# Connectors.net
KiCad netlist of a schematic drawn in Altium Designer
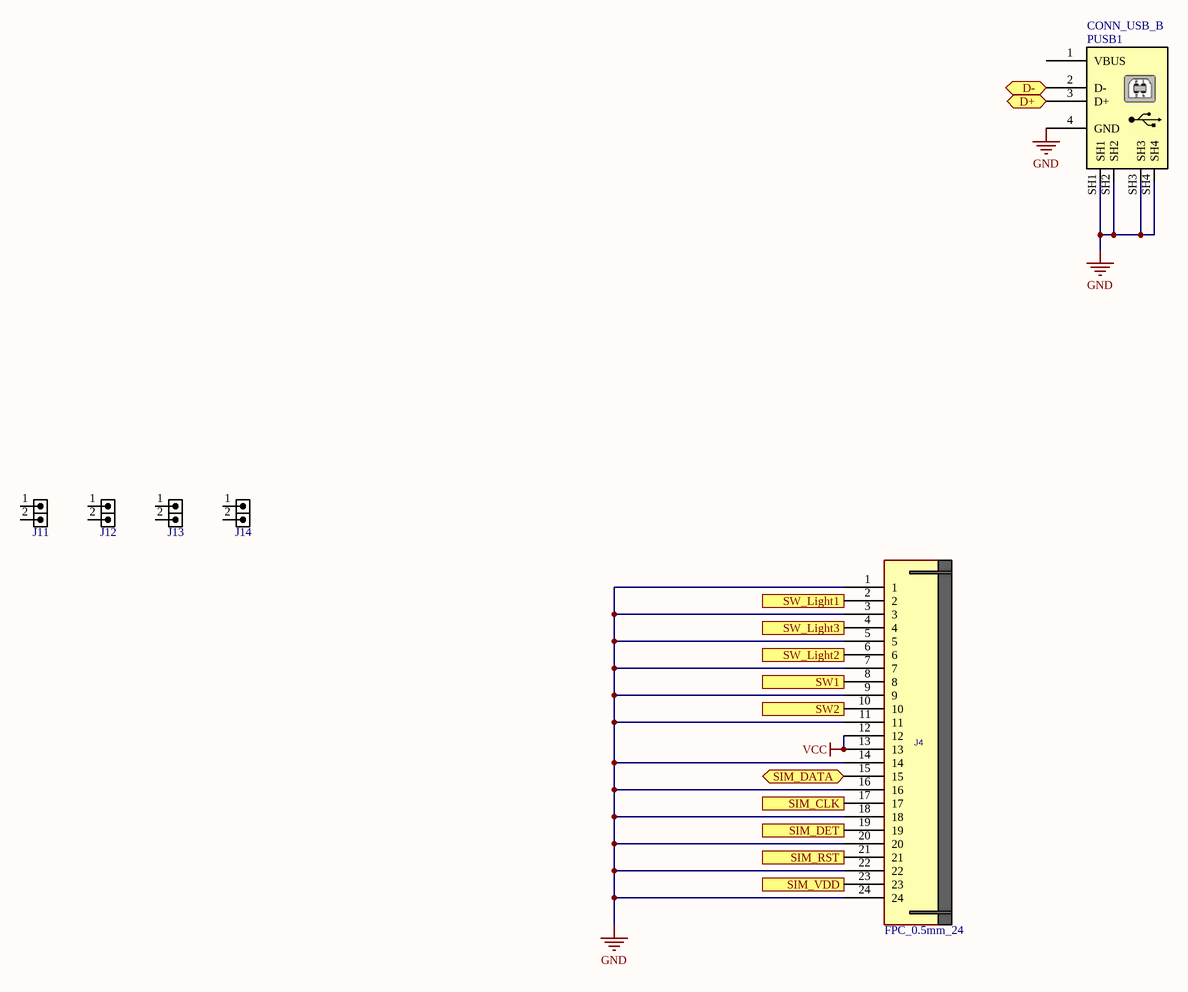
[diagram p0: Connectors.SchDoc]

(export (version "E")
  (design (tool "Eeschema 10.0.6"))
  (components
    (comp (ref "J4")
      (value "FPC_0.5mm_24")
      (description "CONN, FPC, 0.50mm pitch, RightAngle, Bot. Contact")
      (fields
        (field (name "MANF") "MOLEX, Hirose, FCI")
        (field (name "MANF_P#") "52437-2433, FH12-24S-0.5SH(55), SFV24R-1ST")
      )
      (libsource (lib "CONNECTOR") (part "FPC50_24"))
    )
    (comp (ref "J11")
      (value "HDRM2")
      (footprint "HDR_M_1X2")
      (description "CONN, HEADER, Male, pitch: 2.54mm, 2POS")
      (libsource (lib "CONNECTOR HDR") (part "HDR_M_1X2"))
    )
    (comp (ref "J12")
      (value "HDRM2")
      (footprint "HDR_M_1X2")
      (description "CONN, HEADER, Male, pitch: 2.54mm, 2POS")
      (libsource (lib "CONNECTOR HDR") (part "HDR_M_1X2"))
    )
    (comp (ref "J13")
      (value "HDRM2")
      (footprint "HDR_M_1X2")
      (description "CONN, HEADER, Male, pitch: 2.54mm, 2POS")
      (libsource (lib "CONNECTOR HDR") (part "HDR_M_1X2"))
    )
    (comp (ref "J14")
      (value "HDRM2")
      (footprint "HDR_M_1X2")
      (description "CONN, HEADER, Male, pitch: 2.54mm, 2POS")
      (libsource (lib "CONNECTOR HDR") (part "HDR_M_1X2"))
    )
    (comp (ref "PUSB1")
      (value "CONN_USB_B")
      (footprint "USB_B_ST")
      (description "CONN, USB, B, STRAIGHT, THD")
      (libsource (lib "CONNECTOR") (part "USB_B_ST"))
    )
  )
  (nets
    (net (code "1") (name "/D+") (class "Default")
      (node (ref "PUSB1") (pin "3") (pinfunction "D+_3") (pintype "passive"))
    )
    (net (code "2") (name "/D-") (class "Default")
      (node (ref "PUSB1") (pin "2") (pinfunction "D-_2") (pintype "passive"))
    )
    (net (code "3") (name "/SIM_CLK") (class "Default")
      (node (ref "J4") (pin "17") (pinfunction "17_17") (pintype "passive"))
    )
    (net (code "4") (name "/SIM_DATA") (class "Default")
      (node (ref "J4") (pin "15") (pinfunction "15_15") (pintype "passive"))
    )
    (net (code "5") (name "/SIM_DET") (class "Default")
      (node (ref "J4") (pin "19") (pinfunction "19_19") (pintype "passive"))
    )
    (net (code "6") (name "/SIM_RST") (class "Default")
      (node (ref "J4") (pin "21") (pinfunction "21_21") (pintype "passive"))
    )
    (net (code "7") (name "/SIM_VDD") (class "Default")
      (node (ref "J4") (pin "23") (pinfunction "23_23") (pintype "passive"))
    )
    (net (code "8") (name "/SW1") (class "Default")
      (node (ref "J4") (pin "8") (pinfunction "8_8") (pintype "passive"))
    )
    (net (code "9") (name "/SW2") (class "Default")
      (node (ref "J4") (pin "10") (pinfunction "10_10") (pintype "passive"))
    )
    (net (code "10") (name "/SW_Light1") (class "Default")
      (node (ref "J4") (pin "2") (pinfunction "2_2") (pintype "passive"))
    )
    (net (code "11") (name "/SW_Light2") (class "Default")
      (node (ref "J4") (pin "6") (pinfunction "6_6") (pintype "passive"))
    )
    (net (code "12") (name "/SW_Light3") (class "Default")
      (node (ref "J4") (pin "4") (pinfunction "4_4") (pintype "passive"))
    )
    (net (code "13") (name "GND") (class "Default")
      (node (ref "J4") (pin "1") (pinfunction "1_1") (pintype "passive"))
      (node (ref "J4") (pin "11") (pinfunction "11_11") (pintype "passive"))
      (node (ref "J4") (pin "14") (pinfunction "14_14") (pintype "passive"))
      (node (ref "J4") (pin "16") (pinfunction "16_16") (pintype "passive"))
      (node (ref "J4") (pin "18") (pinfunction "18_18") (pintype "passive"))
      (node (ref "J4") (pin "20") (pinfunction "20_20") (pintype "passive"))
      (node (ref "J4") (pin "22") (pinfunction "22_22") (pintype "passive"))
      (node (ref "J4") (pin "24") (pinfunction "24_24") (pintype "passive"))
      (node (ref "J4") (pin "3") (pinfunction "3_3") (pintype "passive"))
      (node (ref "J4") (pin "5") (pinfunction "5_5") (pintype "passive"))
      (node (ref "J4") (pin "7") (pinfunction "7_7") (pintype "passive"))
      (node (ref "J4") (pin "9") (pinfunction "9_9") (pintype "passive"))
      (node (ref "PUSB1") (pin "4") (pinfunction "GND_4") (pintype "power_in"))
      (node (ref "PUSB1") (pin "SH1") (pinfunction "SH1_SH1") (pintype "passive"))
      (node (ref "PUSB1") (pin "SH2") (pinfunction "SH2_SH2") (pintype "passive"))
      (node (ref "PUSB1") (pin "SH3") (pinfunction "SH3_SH3") (pintype "passive"))
      (node (ref "PUSB1") (pin "SH4") (pinfunction "SH4_SH4") (pintype "passive"))
    )
    (net (code "14") (name "VCC") (class "Default")
      (node (ref "J4") (pin "12") (pinfunction "12_12") (pintype "passive"))
      (node (ref "J4") (pin "13") (pinfunction "13_13") (pintype "passive"))
    )
    (net (code "15") (name "unconnected-(J11-Pad1)") (class "Default")
      (node (ref "J11") (pin "1") (pinfunction "1_1") (pintype "passive"))
    )
    (net (code "16") (name "unconnected-(J11-Pad2)") (class "Default")
      (node (ref "J11") (pin "2") (pinfunction "2_2") (pintype "passive"))
    )
    (net (code "17") (name "unconnected-(J12-Pad1)") (class "Default")
      (node (ref "J12") (pin "1") (pinfunction "1_1") (pintype "passive"))
    )
    (net (code "18") (name "unconnected-(J12-Pad2)") (class "Default")
      (node (ref "J12") (pin "2") (pinfunction "2_2") (pintype "passive"))
    )
    (net (code "19") (name "unconnected-(J13-Pad1)") (class "Default")
      (node (ref "J13") (pin "1") (pinfunction "1_1") (pintype "passive"))
    )
    (net (code "20") (name "unconnected-(J13-Pad2)") (class "Default")
      (node (ref "J13") (pin "2") (pinfunction "2_2") (pintype "passive"))
    )
    (net (code "21") (name "unconnected-(J14-Pad1)") (class "Default")
      (node (ref "J14") (pin "1") (pinfunction "1_1") (pintype "passive"))
    )
    (net (code "22") (name "unconnected-(J14-Pad2)") (class "Default")
      (node (ref "J14") (pin "2") (pinfunction "2_2") (pintype "passive"))
    )
    (net (code "23") (name "unconnected-(PUSB1-VBUS-Pad1)") (class "Default")
      (node (ref "PUSB1") (pin "1") (pinfunction "VBUS_1") (pintype "power_in"))
    )
  )
)
